# Vibration_Sensor_Schematic_Rev1.net
KiCad netlist of a schematic drawn in EAGLE
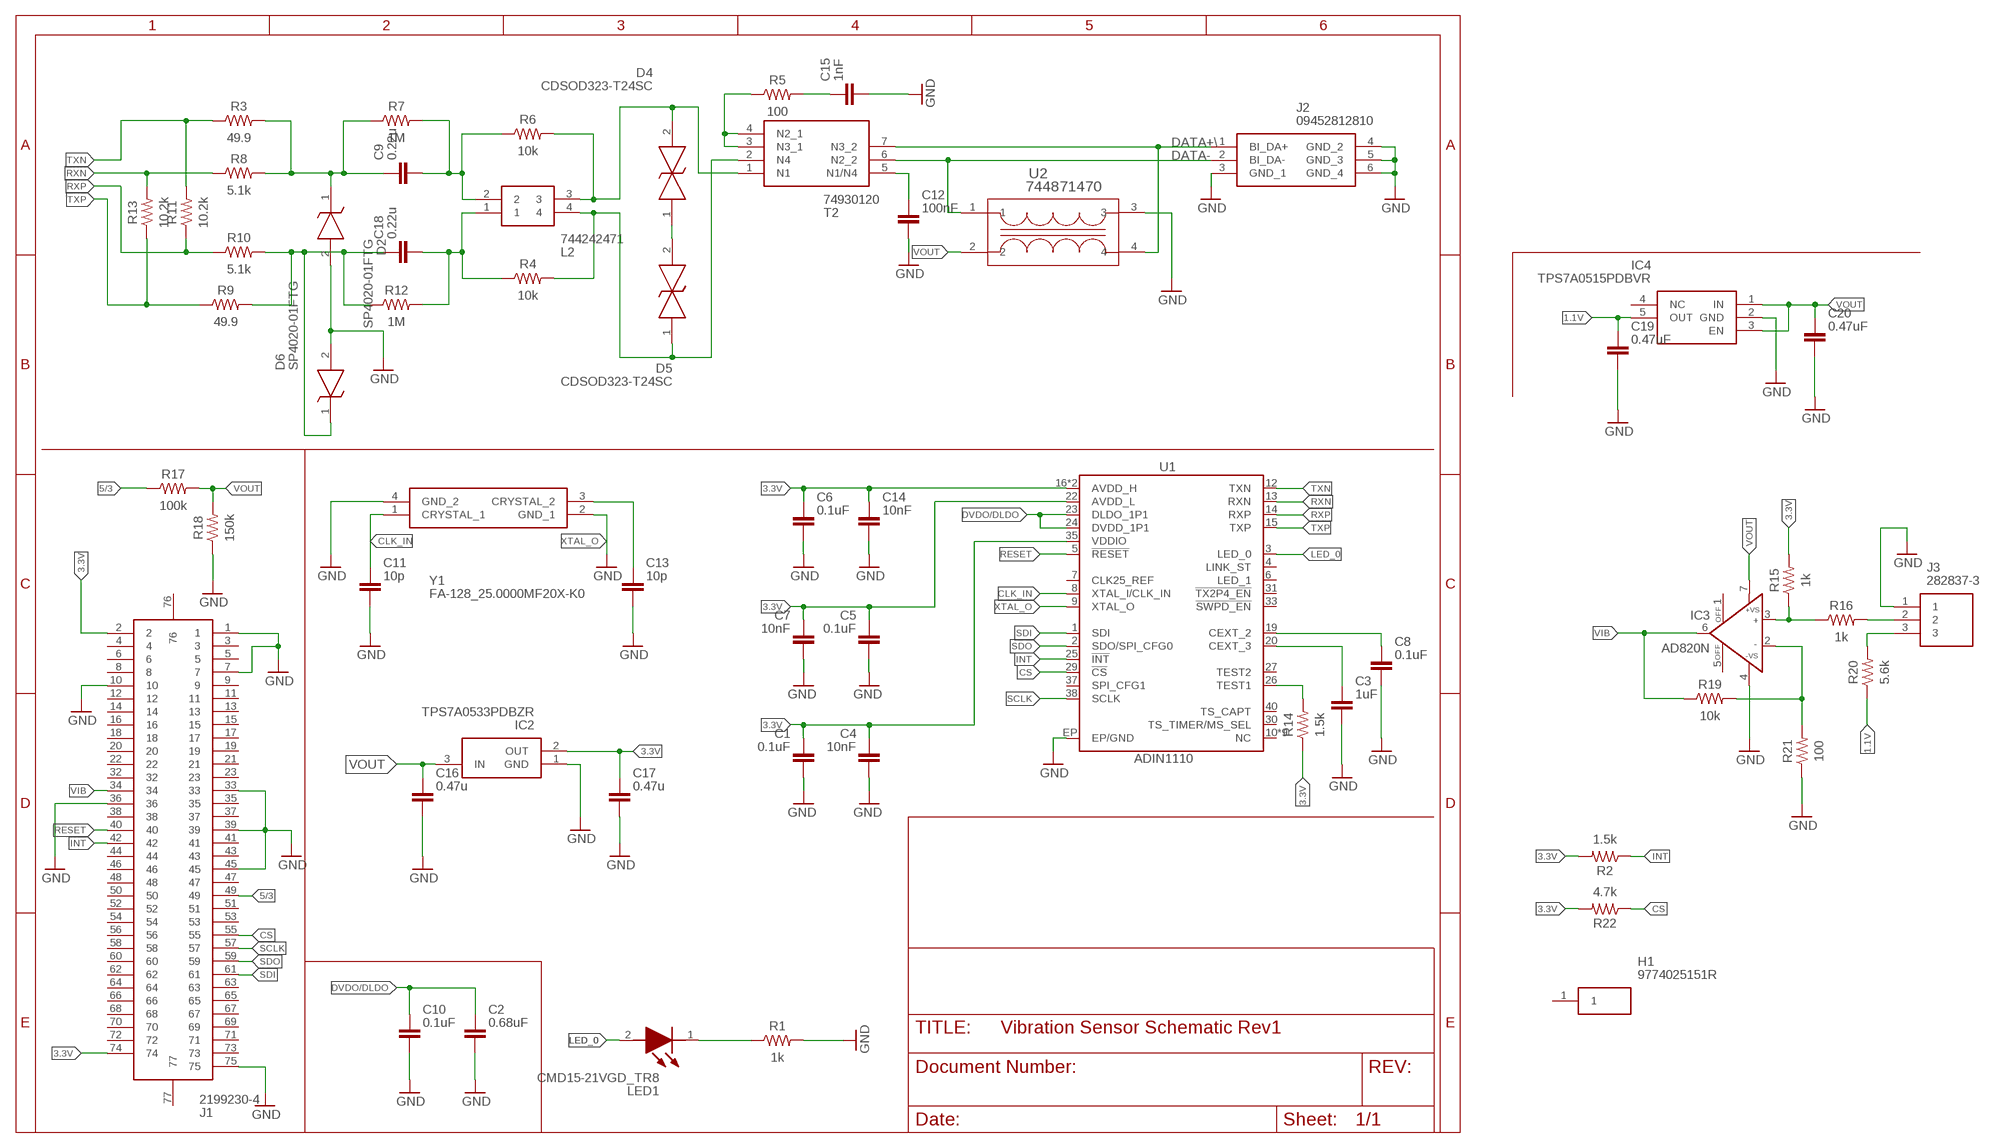
[diagram p0: schematic, sheet 1]

(export (version "E")
  (design (tool "Eeschema 10.0.6"))
  (components
    (comp (ref "C1")
      (value "0.1uF")
      (footprint "eagle-import:CAPC1005X60")
      (libsource (lib "eagle-import") (part "CCHIP-0402(1005-METRIC)_"))
    )
    (comp (ref "C2")
      (value "0.68uF")
      (footprint "eagle-import:CAPC1005X60")
      (libsource (lib "eagle-import") (part "CCHIP-0402(1005-METRIC)_"))
    )
    (comp (ref "C3")
      (value "1uF")
      (footprint "eagle-import:CAPC1005X60")
      (libsource (lib "eagle-import") (part "CCHIP-0402(1005-METRIC)_"))
    )
    (comp (ref "C4")
      (value "10nF")
      (footprint "eagle-import:CAPC1005X60")
      (libsource (lib "eagle-import") (part "CCHIP-0402(1005-METRIC)_"))
    )
    (comp (ref "C5")
      (value "0.1uF")
      (footprint "eagle-import:CAPC1005X60")
      (libsource (lib "eagle-import") (part "CCHIP-0402(1005-METRIC)_"))
    )
    (comp (ref "C6")
      (value "0.1uF")
      (footprint "eagle-import:CAPC1005X60")
      (libsource (lib "eagle-import") (part "CCHIP-0402(1005-METRIC)_"))
    )
    (comp (ref "C7")
      (value "10nF")
      (footprint "eagle-import:CAPC1005X60")
      (libsource (lib "eagle-import") (part "CCHIP-0402(1005-METRIC)_"))
    )
    (comp (ref "C8")
      (value "0.1uF")
      (footprint "eagle-import:CAPC1005X60")
      (libsource (lib "eagle-import") (part "CCHIP-0402(1005-METRIC)_"))
    )
    (comp (ref "C9")
      (value "0.22u")
      (footprint "eagle-import:CAPC1005X60")
      (libsource (lib "eagle-import") (part "CCHIP-0402(1005-METRIC)_"))
    )
    (comp (ref "C10")
      (value "0.1uF")
      (footprint "eagle-import:CAPC1005X60")
      (libsource (lib "eagle-import") (part "CCHIP-0402(1005-METRIC)_"))
    )
    (comp (ref "C11")
      (value "10p")
      (footprint "eagle-import:CAPC1005X60")
      (libsource (lib "eagle-import") (part "CCHIP-0402(1005-METRIC)_"))
    )
    (comp (ref "C12")
      (value "100nF")
      (footprint "eagle-import:CAPC1005X60")
      (libsource (lib "eagle-import") (part "CCHIP-0402(1005-METRIC)_"))
    )
    (comp (ref "C13")
      (value "10p")
      (footprint "eagle-import:CAPC1005X60")
      (libsource (lib "eagle-import") (part "CCHIP-0402(1005-METRIC)_"))
    )
    (comp (ref "C14")
      (value "10nF")
      (footprint "eagle-import:CAPC1005X60")
      (libsource (lib "eagle-import") (part "CCHIP-0402(1005-METRIC)_"))
    )
    (comp (ref "C15")
      (value "1nF")
      (footprint "eagle-import:CAPC1005X60")
      (libsource (lib "eagle-import") (part "CCHIP-0402(1005-METRIC)_"))
    )
    (comp (ref "C16")
      (value "0.47u")
      (footprint "eagle-import:CAPC1005X60")
      (libsource (lib "eagle-import") (part "CCHIP-0402(1005-METRIC)_"))
    )
    (comp (ref "C17")
      (value "0.47u")
      (footprint "eagle-import:CAPC1005X60")
      (libsource (lib "eagle-import") (part "CCHIP-0402(1005-METRIC)_"))
    )
    (comp (ref "C18")
      (value "0.22u")
      (footprint "eagle-import:CAPC1005X60")
      (libsource (lib "eagle-import") (part "CCHIP-0402(1005-METRIC)_"))
    )
    (comp (ref "C19")
      (value "0.47uF")
      (footprint "eagle-import:CAPC1005X60")
      (libsource (lib "eagle-import") (part "CCHIP-0402(1005-METRIC)_"))
    )
    (comp (ref "C20")
      (value "0.47uF")
      (footprint "eagle-import:CAPC1005X60")
      (libsource (lib "eagle-import") (part "CCHIP-0402(1005-METRIC)_"))
    )
    (comp (ref "D2")
      (value "SP4020-01FTG")
      (footprint "eagle-import:SOD2613X114N")
      (fields (field (name "MOUSER_PART_NUMBER") "576-SP4020-01FTG"))
      (libsource (lib "eagle-import") (part "SP4020-01FTG"))
    )
    (comp (ref "D4")
      (value "CDSOD323-T24SC")
      (footprint "eagle-import:SOD2513X114N")
      (fields (field (name "MOUSER_PART_NUMBER") "652-CDSOD323-T24SC"))
      (libsource (lib "eagle-import") (part "CDSOD323-T24SC"))
    )
    (comp (ref "D5")
      (value "CDSOD323-T24SC")
      (footprint "eagle-import:SOD2513X114N")
      (fields (field (name "MOUSER_PART_NUMBER") "652-CDSOD323-T24SC"))
      (libsource (lib "eagle-import") (part "CDSOD323-T24SC"))
    )
    (comp (ref "D6")
      (value "SP4020-01FTG")
      (footprint "eagle-import:SOD2613X114N")
      (fields (field (name "MOUSER_PART_NUMBER") "576-SP4020-01FTG"))
      (libsource (lib "eagle-import") (part "SP4020-01FTG"))
    )
    (comp (ref "H1")
      (value "9774025151R")
      (footprint "eagle-import:9774025151R")
      (fields (field (name "MOUSER_PART_NUMBER") "710-9774025151R"))
      (libsource (lib "eagle-import") (part "9774025151R"))
    )
    (comp (ref "IC2")
      (value "TPS7A0533PDBZR")
      (footprint "eagle-import:SOT95P237X112-3N")
      (fields (field (name "MOUSER_PART_NUMBER") "595-TPS7A0533PDBZR"))
      (libsource (lib "eagle-import") (part "TPS7A0533PDBZR"))
    )
    (comp (ref "IC3")
      (value "AD820N")
      (footprint "eagle-import:DIL08")
      (libsource (lib "eagle-import") (part "AD820N"))
    )
    (comp (ref "IC4")
      (value "TPS7A0515PDBVR")
      (footprint "eagle-import:SOT95P280X145-5N")
      (fields (field (name "MOUSER_PART_NUMBER") "595-TPS7A0515PDBVR"))
      (libsource (lib "eagle-import") (part "TPS7A0515PDBVR"))
    )
    (comp (ref "J1")
      (value "2199230-4")
      (footprint "eagle-import:21992304")
      (fields (field (name "MOUSER_PART_NUMBER") "571-2199230-4"))
      (libsource (lib "eagle-import") (part "2199230-4"))
    )
    (comp (ref "J2")
      (value "09452812810")
      (footprint "eagle-import:09452812810")
      (fields (field (name "MOUSER_PART_NUMBER") "617-09452812810"))
      (libsource (lib "eagle-import") (part "09452812810"))
    )
    (comp (ref "J3")
      (value "282837-3")
      (footprint "eagle-import:2828373")
      (fields (field (name "MOUSER_PART_NUMBER") "571-2828373"))
      (libsource (lib "eagle-import") (part "282837-3"))
    )
    (comp (ref "L2")
      (value "744242471")
      (footprint "eagle-import:744242471")
      (fields (field (name "MOUSER_PART_NUMBER") "710-744242471"))
      (libsource (lib "eagle-import") (part "744242471"))
    )
    (comp (ref "LED1")
      (value "CMD15-21VGD_TR8")
      (footprint "eagle-import:LEDC3215X130N")
      (fields
        (field (name "ARROW_PART_NUMBER") "CMD15-21VGD/TR8")
        (field (name "MOUSER_PART_NUMBER") "606-CMD15-21VGD/TR8")
      )
      (libsource (lib "eagle-import") (part "CMD15-21VGD_TR8"))
    )
    (comp (ref "R1")
      (value "1k")
      (footprint "eagle-import:RESC1005X40")
      (libsource (lib "eagle-import") (part "R-USCHIP-0402(1005-METRIC)_"))
    )
    (comp (ref "R2")
      (value "1.5k")
      (footprint "eagle-import:RESC1005X40")
      (libsource (lib "eagle-import") (part "R-USCHIP-0402(1005-METRIC)_"))
    )
    (comp (ref "R3")
      (value "49.9")
      (footprint "eagle-import:RESC1005X40")
      (libsource (lib "eagle-import") (part "R-USCHIP-0402(1005-METRIC)_"))
    )
    (comp (ref "R4")
      (value "10k")
      (footprint "eagle-import:RESC1005X40")
      (libsource (lib "eagle-import") (part "R-USCHIP-0402(1005-METRIC)_"))
    )
    (comp (ref "R5")
      (value "100")
      (footprint "eagle-import:RESC1005X40")
      (libsource (lib "eagle-import") (part "R-USCHIP-0402(1005-METRIC)_"))
    )
    (comp (ref "R6")
      (value "10k")
      (footprint "eagle-import:RESC1005X40")
      (libsource (lib "eagle-import") (part "R-USCHIP-0402(1005-METRIC)_"))
    )
    (comp (ref "R7")
      (value "1M")
      (footprint "eagle-import:RESC1005X40")
      (libsource (lib "eagle-import") (part "R-USCHIP-0402(1005-METRIC)_"))
    )
    (comp (ref "R8")
      (value "5.1k")
      (footprint "eagle-import:RESC1005X40")
      (libsource (lib "eagle-import") (part "R-USCHIP-0402(1005-METRIC)_"))
    )
    (comp (ref "R9")
      (value "49.9")
      (footprint "eagle-import:RESC1005X40")
      (libsource (lib "eagle-import") (part "R-USCHIP-0402(1005-METRIC)_"))
    )
    (comp (ref "R10")
      (value "5.1k")
      (footprint "eagle-import:RESC1005X40")
      (libsource (lib "eagle-import") (part "R-USCHIP-0402(1005-METRIC)_"))
    )
    (comp (ref "R11")
      (value "10.2k")
      (footprint "eagle-import:RESC1005X40")
      (libsource (lib "eagle-import") (part "R-USCHIP-0402(1005-METRIC)_"))
    )
    (comp (ref "R12")
      (value "1M")
      (footprint "eagle-import:RESC1005X40")
      (libsource (lib "eagle-import") (part "R-USCHIP-0402(1005-METRIC)_"))
    )
    (comp (ref "R13")
      (value "10.2k")
      (footprint "eagle-import:RESC1005X40")
      (libsource (lib "eagle-import") (part "R-USCHIP-0402(1005-METRIC)_"))
    )
    (comp (ref "R14")
      (value "1.5k")
      (footprint "eagle-import:RESC1005X40")
      (libsource (lib "eagle-import") (part "R-USCHIP-0402(1005-METRIC)_"))
    )
    (comp (ref "R15")
      (value "1k")
      (footprint "eagle-import:RESC1005X40")
      (libsource (lib "eagle-import") (part "R-USCHIP-0402(1005-METRIC)_"))
    )
    (comp (ref "R16")
      (value "1k")
      (footprint "eagle-import:RESC1005X40")
      (libsource (lib "eagle-import") (part "R-USCHIP-0402(1005-METRIC)_"))
    )
    (comp (ref "R17")
      (value "100k")
      (footprint "eagle-import:RESC1005X40")
      (libsource (lib "eagle-import") (part "R-USCHIP-0402(1005-METRIC)_"))
    )
    (comp (ref "R18")
      (value "150k")
      (footprint "eagle-import:RESC1005X40")
      (libsource (lib "eagle-import") (part "R-USCHIP-0402(1005-METRIC)_"))
    )
    (comp (ref "R19")
      (value "10k")
      (footprint "eagle-import:RESC1005X40")
      (libsource (lib "eagle-import") (part "R-USCHIP-0402(1005-METRIC)_"))
    )
    (comp (ref "R20")
      (value "5.6k")
      (footprint "eagle-import:RESC1005X40")
      (libsource (lib "eagle-import") (part "R-USCHIP-0402(1005-METRIC)_"))
    )
    (comp (ref "R21")
      (value "100")
      (footprint "eagle-import:RESC1005X40")
      (libsource (lib "eagle-import") (part "R-USCHIP-0402(1005-METRIC)_"))
    )
    (comp (ref "R22")
      (value "4.7k")
      (footprint "eagle-import:RESC1005X40")
      (libsource (lib "eagle-import") (part "R-USCHIP-0402(1005-METRIC)_"))
    )
    (comp (ref "T2")
      (value "74930120")
      (footprint "eagle-import:74930120")
      (fields (field (name "MOUSER_PART_NUMBER") "710-74930120"))
      (libsource (lib "eagle-import") (part "74930120"))
    )
    (comp (ref "U1")
      (value "ADIN1110")
      (footprint "eagle-import:LFCSP-40")
      (libsource (lib "eagle-import") (part "ADIN1110"))
    )
    (comp (ref "U2")
      (value "744871470")
      (footprint "eagle-import:SMT_871470_WRE")
      (fields (field (name "COPYRIGHT") "Copyright (C) 2023 Ultra Librarian. All rights reserved."))
      (libsource (lib "eagle-import") (part "744871470"))
    )
    (comp (ref "Y1")
      (value "FA-128_25.0000MF20X-K0")
      (footprint "eagle-import:FA128250000MF20XK0")
      (fields
        (field (name "MANUFACTURER_PART_NUMBER") "FA-128 25.0000MF20X-K0")
        (field (name "MOUSER_PART_NUMBER") "732-FA-12825F20X-K0")
      )
      (libsource (lib "eagle-import") (part "FA-128_25.0000MF20X-K0"))
    )
  )
  (nets
    (net (code "1") (name "/DATA+\\") (class "Default")
      (node (ref "J2") (pin "1") (pinfunction "BI_DA+_1") (pintype "bidirectional"))
      (node (ref "T2") (pin "7") (pinfunction "N3_2_7") (pintype "bidirectional"))
      (node (ref "U2") (pin "4") (pinfunction "4_4") (pintype "passive"))
    )
    (net (code "2") (name "/DATA-") (class "Default")
      (node (ref "J2") (pin "2") (pinfunction "BI_DA-_2") (pintype "bidirectional"))
      (node (ref "T2") (pin "6") (pinfunction "N2_2_6") (pintype "bidirectional"))
      (node (ref "U2") (pin "1") (pinfunction "1_1") (pintype "passive"))
    )
    (net (code "3") (name "1.1V") (class "Default")
      (node (ref "C19") (pin "1") (pinfunction "1_1") (pintype "passive"))
      (node (ref "IC4") (pin "5") (pinfunction "OUT_5") (pintype "bidirectional"))
      (node (ref "R20") (pin "1") (pinfunction "1_1") (pintype "passive"))
    )
    (net (code "4") (name "3.3V") (class "Default")
      (node (ref "C1") (pin "1") (pinfunction "1_1") (pintype "passive"))
      (node (ref "C14") (pin "1") (pinfunction "1_1") (pintype "passive"))
      (node (ref "C17") (pin "1") (pinfunction "1_1") (pintype "passive"))
      (node (ref "C4") (pin "1") (pinfunction "1_1") (pintype "passive"))
      (node (ref "C5") (pin "1") (pinfunction "1_1") (pintype "passive"))
      (node (ref "C6") (pin "1") (pinfunction "1_1") (pintype "passive"))
      (node (ref "C7") (pin "1") (pinfunction "1_1") (pintype "passive"))
      (node (ref "IC2") (pin "2") (pinfunction "OUT_2") (pintype "output"))
      (node (ref "J1") (pin "2") (pinfunction "2_2") (pintype "bidirectional"))
      (node (ref "J1") (pin "74") (pinfunction "74_74") (pintype "bidirectional"))
      (node (ref "R14") (pin "1") (pinfunction "1_1") (pintype "passive"))
      (node (ref "R15") (pin "2") (pinfunction "2_2") (pintype "passive"))
      (node (ref "R2") (pin "2") (pinfunction "2_2") (pintype "passive"))
      (node (ref "R22") (pin "2") (pinfunction "2_2") (pintype "passive"))
      (node (ref "U1") (pin "16") (pinfunction "AVDD_H_16") (pintype "bidirectional"))
      (node (ref "U1") (pin "17") (pinfunction "AVDD_H_17") (pintype "bidirectional"))
      (node (ref "U1") (pin "22") (pinfunction "AVDD_L_22") (pintype "bidirectional"))
      (node (ref "U1") (pin "35") (pinfunction "VDDIO_35") (pintype "bidirectional"))
    )
    (net (code "5") (name "5{slash}3") (class "Default")
      (node (ref "J1") (pin "49") (pinfunction "49_49") (pintype "bidirectional"))
      (node (ref "R17") (pin "1") (pinfunction "1_1") (pintype "passive"))
    )
    (net (code "6") (name "CLK_IN") (class "Default")
      (node (ref "C11") (pin "1") (pinfunction "1_1") (pintype "passive"))
      (node (ref "U1") (pin "8") (pinfunction "XTAL_I/CLK_IN_8") (pintype "bidirectional"))
      (node (ref "Y1") (pin "1") (pinfunction "CRYSTAL_1_1") (pintype "bidirectional"))
    )
    (net (code "7") (name "CS") (class "Default")
      (node (ref "J1") (pin "55") (pinfunction "55_55") (pintype "bidirectional"))
      (node (ref "R22") (pin "1") (pinfunction "1_1") (pintype "passive"))
      (node (ref "U1") (pin "29") (pinfunction "~{CS}_29") (pintype "bidirectional"))
    )
    (net (code "8") (name "DVDO{slash}DLDO") (class "Default")
      (node (ref "C10") (pin "1") (pinfunction "1_1") (pintype "passive"))
      (node (ref "C2") (pin "1") (pinfunction "1_1") (pintype "passive"))
      (node (ref "U1") (pin "23") (pinfunction "DLDO_1P1_23") (pintype "bidirectional"))
      (node (ref "U1") (pin "24") (pinfunction "DVDD_1P1_24") (pintype "bidirectional"))
    )
    (net (code "9") (name "GND") (class "Default")
      (node (ref "C1") (pin "2") (pinfunction "2_2") (pintype "passive"))
      (node (ref "C10") (pin "2") (pinfunction "2_2") (pintype "passive"))
      (node (ref "C11") (pin "2") (pinfunction "2_2") (pintype "passive"))
      (node (ref "C12") (pin "2") (pinfunction "2_2") (pintype "passive"))
      (node (ref "C13") (pin "2") (pinfunction "2_2") (pintype "passive"))
      (node (ref "C14") (pin "2") (pinfunction "2_2") (pintype "passive"))
      (node (ref "C15") (pin "2") (pinfunction "2_2") (pintype "passive"))
      (node (ref "C16") (pin "2") (pinfunction "2_2") (pintype "passive"))
      (node (ref "C17") (pin "2") (pinfunction "2_2") (pintype "passive"))
      (node (ref "C19") (pin "2") (pinfunction "2_2") (pintype "passive"))
      (node (ref "C2") (pin "2") (pinfunction "2_2") (pintype "passive"))
      (node (ref "C20") (pin "2") (pinfunction "2_2") (pintype "passive"))
      (node (ref "C3") (pin "2") (pinfunction "2_2") (pintype "passive"))
      (node (ref "C4") (pin "2") (pinfunction "2_2") (pintype "passive"))
      (node (ref "C5") (pin "2") (pinfunction "2_2") (pintype "passive"))
      (node (ref "C6") (pin "2") (pinfunction "2_2") (pintype "passive"))
      (node (ref "C7") (pin "2") (pinfunction "2_2") (pintype "passive"))
      (node (ref "C8") (pin "2") (pinfunction "2_2") (pintype "passive"))
      (node (ref "D2") (pin "2") (pinfunction "A_2") (pintype "bidirectional"))
      (node (ref "D6") (pin "2") (pinfunction "A_2") (pintype "bidirectional"))
      (node (ref "IC2") (pin "1") (pinfunction "GND_1") (pintype "power_in"))
      (node (ref "IC3") (pin "4") (pinfunction "-VS_4") (pintype "input"))
      (node (ref "IC4") (pin "2") (pinfunction "GND_2") (pintype "bidirectional"))
      (node (ref "J1") (pin "1") (pinfunction "1_1") (pintype "bidirectional"))
      (node (ref "J1") (pin "10") (pinfunction "10_10") (pintype "bidirectional"))
      (node (ref "J1") (pin "33") (pinfunction "33_33") (pintype "bidirectional"))
      (node (ref "J1") (pin "36") (pinfunction "36_36") (pintype "bidirectional"))
      (node (ref "J1") (pin "39") (pinfunction "39_39") (pintype "bidirectional"))
      (node (ref "J1") (pin "45") (pinfunction "45_45") (pintype "bidirectional"))
      (node (ref "J1") (pin "7") (pinfunction "7_7") (pintype "bidirectional"))
      (node (ref "J1") (pin "75") (pinfunction "75_75") (pintype "bidirectional"))
      (node (ref "J2") (pin "3") (pinfunction "GND_1_3") (pintype "bidirectional"))
      (node (ref "J2") (pin "4") (pinfunction "GND_2_4") (pintype "bidirectional"))
      (node (ref "J2") (pin "5") (pinfunction "GND_3_5") (pintype "bidirectional"))
      (node (ref "J2") (pin "6") (pinfunction "GND_4_6") (pintype "bidirectional"))
      (node (ref "J3") (pin "1") (pinfunction "1_1") (pintype "bidirectional"))
      (node (ref "R1") (pin "2") (pinfunction "2_2") (pintype "passive"))
      (node (ref "R18") (pin "1") (pinfunction "1_1") (pintype "passive"))
      (node (ref "R21") (pin "1") (pinfunction "1_1") (pintype "passive"))
      (node (ref "U1") (pin "EP") (pinfunction "EP/GND_EP") (pintype "bidirectional"))
      (node (ref "U2") (pin "3") (pinfunction "3_3") (pintype "passive"))
      (node (ref "Y1") (pin "2") (pinfunction "GND_1_2") (pintype "bidirectional"))
      (node (ref "Y1") (pin "4") (pinfunction "GND_2_4") (pintype "bidirectional"))
    )
    (net (code "10") (name "INT") (class "Default")
      (node (ref "J1") (pin "42") (pinfunction "42_42") (pintype "bidirectional"))
      (node (ref "R2") (pin "1") (pinfunction "1_1") (pintype "passive"))
      (node (ref "U1") (pin "25") (pinfunction "~{INT}_25") (pintype "bidirectional"))
    )
    (net (code "11") (name "LED_0") (class "Default")
      (node (ref "LED1") (pin "2") (pinfunction "A_2") (pintype "bidirectional"))
      (node (ref "U1") (pin "3") (pinfunction "LED_0_3") (pintype "bidirectional"))
    )
    (net (code "12") (name "Net-(C9-Pad2)") (class "Default")
      (node (ref "C9") (pin "2") (pinfunction "2_2") (pintype "passive"))
      (node (ref "L2") (pin "2") (pinfunction "2_2") (pintype "bidirectional"))
      (node (ref "R6") (pin "1") (pinfunction "1_1") (pintype "passive"))
      (node (ref "R7") (pin "2") (pinfunction "2_2") (pintype "passive"))
    )
    (net (code "13") (name "Net-(C15-Pad1)") (class "Default")
      (node (ref "C15") (pin "1") (pinfunction "1_1") (pintype "passive"))
      (node (ref "R5") (pin "2") (pinfunction "2_2") (pintype "passive"))
    )
    (net (code "14") (name "Net-(C18-Pad2)") (class "Default")
      (node (ref "C18") (pin "2") (pinfunction "2_2") (pintype "passive"))
      (node (ref "L2") (pin "1") (pinfunction "1_1") (pintype "bidirectional"))
      (node (ref "R12") (pin "2") (pinfunction "2_2") (pintype "passive"))
      (node (ref "R4") (pin "1") (pinfunction "1_1") (pintype "passive"))
    )
    (net (code "15") (name "Net-(D2-K)") (class "Default")
      (node (ref "C9") (pin "1") (pinfunction "1_1") (pintype "passive"))
      (node (ref "D2") (pin "1") (pinfunction "K_1") (pintype "bidirectional"))
      (node (ref "R3") (pin "2") (pinfunction "2_2") (pintype "passive"))
      (node (ref "R7") (pin "1") (pinfunction "1_1") (pintype "passive"))
      (node (ref "R8") (pin "2") (pinfunction "2_2") (pintype "passive"))
    )
    (net (code "16") (name "Net-(D4-Pad1)") (class "Default")
      (node (ref "D4") (pin "1") (pinfunction "1_1") (pintype "bidirectional"))
      (node (ref "D5") (pin "2") (pinfunction "2_2") (pintype "bidirectional"))
    )
    (net (code "17") (name "Net-(D6-K)") (class "Default")
      (node (ref "C18") (pin "1") (pinfunction "1_1") (pintype "passive"))
      (node (ref "D6") (pin "1") (pinfunction "K_1") (pintype "bidirectional"))
      (node (ref "R10") (pin "2") (pinfunction "2_2") (pintype "passive"))
      (node (ref "R12") (pin "1") (pinfunction "1_1") (pintype "passive"))
      (node (ref "R9") (pin "2") (pinfunction "2_2") (pintype "passive"))
    )
    (net (code "18") (name "Net-(IC3-IN+)") (class "Default")
      (node (ref "IC3") (pin "3") (pinfunction "IN+_3") (pintype "input"))
      (node (ref "R15") (pin "1") (pinfunction "1_1") (pintype "passive"))
      (node (ref "R16") (pin "1") (pinfunction "1_1") (pintype "passive"))
    )
    (net (code "19") (name "Net-(IC3-IN-)") (class "Default")
      (node (ref "IC3") (pin "2") (pinfunction "IN-_2") (pintype "input"))
      (node (ref "R19") (pin "2") (pinfunction "2_2") (pintype "passive"))
      (node (ref "R21") (pin "2") (pinfunction "2_2") (pintype "passive"))
    )
    (net (code "20") (name "Net-(J3-Pad2)") (class "Default")
      (node (ref "J3") (pin "2") (pinfunction "2_2") (pintype "bidirectional"))
      (node (ref "R16") (pin "2") (pinfunction "2_2") (pintype "passive"))
    )
    (net (code "21") (name "Net-(J3-Pad3)") (class "Default")
      (node (ref "J3") (pin "3") (pinfunction "3_3") (pintype "bidirectional"))
      (node (ref "R20") (pin "2") (pinfunction "2_2") (pintype "passive"))
    )
    (net (code "22") (name "Net-(LED1-K)") (class "Default")
      (node (ref "LED1") (pin "1") (pinfunction "K_1") (pintype "bidirectional"))
      (node (ref "R1") (pin "1") (pinfunction "1_1") (pintype "passive"))
    )
    (net (code "23") (name "Net-(T2-N1)") (class "Default")
      (node (ref "D4") (pin "2") (pinfunction "2_2") (pintype "bidirectional"))
      (node (ref "L2") (pin "3") (pinfunction "3_3") (pintype "bidirectional"))
      (node (ref "R6") (pin "2") (pinfunction "2_2") (pintype "passive"))
      (node (ref "T2") (pin "1") (pinfunction "N1_1") (pintype "bidirectional"))
    )
    (net (code "24") (name "Net-(T2-N1{slash}N4)") (class "Default")
      (node (ref "C12") (pin "1") (pinfunction "1_1") (pintype "passive"))
      (node (ref "T2") (pin "5") (pinfunction "N1/N4_5") (pintype "bidirectional"))
    )
    (net (code "25") (name "Net-(T2-N2_1)") (class "Default")
      (node (ref "R5") (pin "1") (pinfunction "1_1") (pintype "passive"))
      (node (ref "T2") (pin "3") (pinfunction "N3_1_3") (pintype "bidirectional"))
      (node (ref "T2") (pin "4") (pinfunction "N2_1_4") (pintype "bidirectional"))
    )
    (net (code "26") (name "Net-(T2-N4)") (class "Default")
      (node (ref "D5") (pin "1") (pinfunction "1_1") (pintype "bidirectional"))
      (node (ref "L2") (pin "4") (pinfunction "4_4") (pintype "bidirectional"))
      (node (ref "R4") (pin "2") (pinfunction "2_2") (pintype "passive"))
      (node (ref "T2") (pin "2") (pinfunction "N4_2") (pintype "bidirectional"))
    )
    (net (code "27") (name "Net-(U1-CEXT_2)") (class "Default")
      (node (ref "C8") (pin "1") (pinfunction "1_1") (pintype "passive"))
      (node (ref "U1") (pin "19") (pinfunction "CEXT_2_19") (pintype "bidirectional"))
    )
    (net (code "28") (name "Net-(U1-CEXT_3)") (class "Default")
      (node (ref "C3") (pin "1") (pinfunction "1_1") (pintype "passive"))
      (node (ref "U1") (pin "20") (pinfunction "CEXT_3_20") (pintype "bidirectional"))
    )
    (net (code "29") (name "Net-(U1-TEST1)") (class "Default")
      (node (ref "R14") (pin "2") (pinfunction "2_2") (pintype "passive"))
      (node (ref "U1") (pin "26") (pinfunction "TEST1_26") (pintype "bidirectional"))
    )
    (net (code "30") (name "RESET") (class "Default")
      (node (ref "J1") (pin "40") (pinfunction "40_40") (pintype "bidirectional"))
      (node (ref "U1") (pin "5") (pinfunction "~{RESET}_5") (pintype "bidirectional"))
    )
    (net (code "31") (name "RXN") (class "Default")
      (node (ref "R13") (pin "2") (pinfunction "2_2") (pintype "passive"))
      (node (ref "R8") (pin "1") (pinfunction "1_1") (pintype "passive"))
      (node (ref "U1") (pin "13") (pinfunction "RXN_13") (pintype "bidirectional"))
    )
    (net (code "32") (name "RXP") (class "Default")
      (node (ref "R10") (pin "1") (pinfunction "1_1") (pintype "passive"))
      (node (ref "R11") (pin "1") (pinfunction "1_1") (pintype "passive"))
      (node (ref "U1") (pin "14") (pinfunction "RXP_14") (pintype "bidirectional"))
    )
    (net (code "33") (name "SCLK") (class "Default")
      (node (ref "J1") (pin "57") (pinfunction "57_57") (pintype "bidirectional"))
      (node (ref "U1") (pin "38") (pinfunction "SCLK_38") (pintype "bidirectional"))
    )
    (net (code "34") (name "SDI") (class "Default")
      (node (ref "J1") (pin "61") (pinfunction "61_61") (pintype "bidirectional"))
      (node (ref "U1") (pin "1") (pinfunction "SDI_1") (pintype "bidirectional"))
    )
    (net (code "35") (name "SDO") (class "Default")
      (node (ref "J1") (pin "59") (pinfunction "59_59") (pintype "bidirectional"))
      (node (ref "U1") (pin "2") (pinfunction "SDO/SPI_CFG0_2") (pintype "bidirectional"))
    )
    (net (code "36") (name "TXN") (class "Default")
      (node (ref "R11") (pin "2") (pinfunction "2_2") (pintype "passive"))
      (node (ref "R3") (pin "1") (pinfunction "1_1") (pintype "passive"))
      (node (ref "U1") (pin "12") (pinfunction "TXN_12") (pintype "bidirectional"))
    )
    (net (code "37") (name "TXP") (class "Default")
      (node (ref "R13") (pin "1") (pinfunction "1_1") (pintype "passive"))
      (node (ref "R9") (pin "1") (pinfunction "1_1") (pintype "passive"))
      (node (ref "U1") (pin "15") (pinfunction "TXP_15") (pintype "bidirectional"))
    )
    (net (code "38") (name "VIB") (class "Default")
      (node (ref "IC3") (pin "6") (pinfunction "OUT_6") (pintype "output"))
      (node (ref "J1") (pin "34") (pinfunction "34_34") (pintype "bidirectional"))
      (node (ref "R19") (pin "1") (pinfunction "1_1") (pintype "passive"))
    )
    (net (code "39") (name "VOUT") (class "Default")
      (node (ref "C16") (pin "1") (pinfunction "1_1") (pintype "passive"))
      (node (ref "C20") (pin "1") (pinfunction "1_1") (pintype "passive"))
      (node (ref "IC2") (pin "3") (pinfunction "IN_3") (pintype "input"))
      (node (ref "IC3") (pin "7") (pinfunction "+VS_7") (pintype "input"))
      (node (ref "IC4") (pin "1") (pinfunction "IN_1") (pintype "bidirectional"))
      (node (ref "IC4") (pin "3") (pinfunction "EN_3") (pintype "bidirectional"))
      (node (ref "R17") (pin "2") (pinfunction "2_2") (pintype "passive"))
      (node (ref "R18") (pin "2") (pinfunction "2_2") (pintype "passive"))
      (node (ref "U2") (pin "2") (pinfunction "2_2") (pintype "passive"))
    )
    (net (code "40") (name "XTAL_O") (class "Default")
      (node (ref "C13") (pin "1") (pinfunction "1_1") (pintype "passive"))
      (node (ref "U1") (pin "9") (pinfunction "XTAL_O_9") (pintype "bidirectional"))
      (node (ref "Y1") (pin "3") (pinfunction "CRYSTAL_2_3") (pintype "bidirectional"))
    )
    (net (code "41") (name "unconnected-(H1-Pad1)") (class "Default")
      (node (ref "H1") (pin "1") (pinfunction "1_1") (pintype "bidirectional"))
    )
    (net (code "42") (name "unconnected-(IC3-OFF-Pad1)") (class "Default")
      (node (ref "IC3") (pin "1") (pinfunction "OFF_1") (pintype "passive"))
    )
    (net (code "43") (name "unconnected-(IC3-OFF-Pad5)") (class "Default")
      (node (ref "IC3") (pin "5") (pinfunction "OFF_5") (pintype "passive"))
    )
    (net (code "44") (name "unconnected-(IC4-NC-Pad4)") (class "Default")
      (node (ref "IC4") (pin "4") (pinfunction "NC_4") (pintype "no_connect"))
    )
    (net (code "45") (name "unconnected-(J1-Pad3)") (class "Default")
      (node (ref "J1") (pin "3") (pinfunction "3_3") (pintype "bidirectional"))
    )
    (net (code "46") (name "unconnected-(J1-Pad4)") (class "Default")
      (node (ref "J1") (pin "4") (pinfunction "4_4") (pintype "bidirectional"))
    )
    (net (code "47") (name "unconnected-(J1-Pad5)") (class "Default")
      (node (ref "J1") (pin "5") (pinfunction "5_5") (pintype "bidirectional"))
    )
    (net (code "48") (name "unconnected-(J1-Pad6)") (class "Default")
      (node (ref "J1") (pin "6") (pinfunction "6_6") (pintype "bidirectional"))
    )
    (net (code "49") (name "unconnected-(J1-Pad8)") (class "Default")
      (node (ref "J1") (pin "8") (pinfunction "8_8") (pintype "bidirectional"))
    )
    (net (code "50") (name "unconnected-(J1-Pad9)") (class "Default")
      (node (ref "J1") (pin "9") (pinfunction "9_9") (pintype "bidirectional"))
    )
    (net (code "51") (name "unconnected-(J1-Pad11)") (class "Default")
      (node (ref "J1") (pin "11") (pinfunction "11_11") (pintype "bidirectional"))
    )
    (net (code "52") (name "unconnected-(J1-Pad12)") (class "Default")
      (node (ref "J1") (pin "12") (pinfunction "12_12") (pintype "bidirectional"))
    )
    (net (code "53") (name "unconnected-(J1-Pad13)") (class "Default")
      (node (ref "J1") (pin "13") (pinfunction "13_13") (pintype "bidirectional"))
    )
    (net (code "54") (name "unconnected-(J1-Pad14)") (class "Default")
      (node (ref "J1") (pin "14") (pinfunction "14_14") (pintype "bidirectional"))
    )
    (net (code "55") (name "unconnected-(J1-Pad15)") (class "Default")
      (node (ref "J1") (pin "15") (pinfunction "15_15") (pintype "bidirectional"))
    )
    (net (code "56") (name "unconnected-(J1-Pad16)") (class "Default")
      (node (ref "J1") (pin "16") (pinfunction "16_16") (pintype "bidirectional"))
    )
    (net (code "57") (name "unconnected-(J1-Pad17)") (class "Default")
      (node (ref "J1") (pin "17") (pinfunction "17_17") (pintype "bidirectional"))
    )
    (net (code "58") (name "unconnected-(J1-Pad18)") (class "Default")
      (node (ref "J1") (pin "18") (pinfunction "18_18") (pintype "bidirectional"))
    )
    (net (code "59") (name "unconnected-(J1-Pad19)") (class "Default")
      (node (ref "J1") (pin "19") (pinfunction "19_19") (pintype "bidirectional"))
    )
    (net (code "60") (name "unconnected-(J1-Pad20)") (class "Default")
      (node (ref "J1") (pin "20") (pinfunction "20_20") (pintype "bidirectional"))
    )
    (net (code "61") (name "unconnected-(J1-Pad21)") (class "Default")
      (node (ref "J1") (pin "21") (pinfunction "21_21") (pintype "bidirectional"))
    )
    (net (code "62") (name "unconnected-(J1-Pad22)") (class "Default")
      (node (ref "J1") (pin "22") (pinfunction "22_22") (pintype "bidirectional"))
    )
    (net (code "63") (name "unconnected-(J1-Pad23)") (class "Default")
      (node (ref "J1") (pin "23") (pinfunction "23_23") (pintype "bidirectional"))
    )
    (net (code "64") (name "unconnected-(J1-Pad32)") (class "Default")
      (node (ref "J1") (pin "32") (pinfunction "32_32") (pintype "bidirectional"))
    )
    (net (code "65") (name "unconnected-(J1-Pad35)") (class "Default")
      (node (ref "J1") (pin "35") (pinfunction "35_35") (pintype "bidirectional"))
    )
    (net (code "66") (name "unconnected-(J1-Pad37)") (class "Default")
      (node (ref "J1") (pin "37") (pinfunction "37_37") (pintype "bidirectional"))
    )
    (net (code "67") (name "unconnected-(J1-Pad38)") (class "Default")
      (node (ref "J1") (pin "38") (pinfunction "38_38") (pintype "bidirectional"))
    )
    (net (code "68") (name "unconnected-(J1-Pad41)") (class "Default")
      (node (ref "J1") (pin "41") (pinfunction "41_41") (pintype "bidirectional"))
    )
    (net (code "69") (name "unconnected-(J1-Pad43)") (class "Default")
      (node (ref "J1") (pin "43") (pinfunction "43_43") (pintype "bidirectional"))
    )
    (net (code "70") (name "unconnected-(J1-Pad44)") (class "Default")
      (node (ref "J1") (pin "44") (pinfunction "44_44") (pintype "bidirectional"))
    )
    (net (code "71") (name "unconnected-(J1-Pad46)") (class "Default")
      (node (ref "J1") (pin "46") (pinfunction "46_46") (pintype "bidirectional"))
    )
    (net (code "72") (name "unconnected-(J1-Pad47)") (class "Default")
      (node (ref "J1") (pin "47") (pinfunction "47_47") (pintype "bidirectional"))
    )
    (net (code "73") (name "unconnected-(J1-Pad48)") (class "Default")
      (node (ref "J1") (pin "48") (pinfunction "48_48") (pintype "bidirectional"))
    )
    (net (code "74") (name "unconnected-(J1-Pad50)") (class "Default")
      (node (ref "J1") (pin "50") (pinfunction "50_50") (pintype "bidirectional"))
    )
    (net (code "75") (name "unconnected-(J1-Pad51)") (class "Default")
      (node (ref "J1") (pin "51") (pinfunction "51_51") (pintype "bidirectional"))
    )
    (net (code "76") (name "unconnected-(J1-Pad52)") (class "Default")
      (node (ref "J1") (pin "52") (pinfunction "52_52") (pintype "bidirectional"))
    )
    (net (code "77") (name "unconnected-(J1-Pad53)") (class "Default")
      (node (ref "J1") (pin "53") (pinfunction "53_53") (pintype "bidirectional"))
    )
    (net (code "78") (name "unconnected-(J1-Pad54)") (class "Default")
      (node (ref "J1") (pin "54") (pinfunction "54_54") (pintype "bidirectional"))
    )
    (net (code "79") (name "unconnected-(J1-Pad56)") (class "Default")
      (node (ref "J1") (pin "56") (pinfunction "56_56") (pintype "bidirectional"))
    )
    (net (code "80") (name "unconnected-(J1-Pad58)") (class "Default")
      (node (ref "J1") (pin "58") (pinfunction "58_58") (pintype "bidirectional"))
    )
    (net (code "81") (name "unconnected-(J1-Pad60)") (class "Default")
      (node (ref "J1") (pin "60") (pinfunction "60_60") (pintype "bidirectional"))
    )
    (net (code "82") (name "unconnected-(J1-Pad62)") (class "Default")
      (node (ref "J1") (pin "62") (pinfunction "62_62") (pintype "bidirectional"))
    )
    (net (code "83") (name "unconnected-(J1-Pad63)") (class "Default")
      (node (ref "J1") (pin "63") (pinfunction "63_63") (pintype "bidirectional"))
    )
    (net (code "84") (name "unconnected-(J1-Pad64)") (class "Default")
      (node (ref "J1") (pin "64") (pinfunction "64_64") (pintype "bidirectional"))
    )
    (net (code "85") (name "unconnected-(J1-Pad65)") (class "Default")
      (node (ref "J1") (pin "65") (pinfunction "65_65") (pintype "bidirectional"))
    )
    (net (code "86") (name "unconnected-(J1-Pad66)") (class "Default")
      (node (ref "J1") (pin "66") (pinfunction "66_66") (pintype "bidirectional"))
    )
    (net (code "87") (name "unconnected-(J1-Pad67)") (class "Default")
      (node (ref "J1") (pin "67") (pinfunction "67_67") (pintype "bidirectional"))
    )
    (net (code "88") (name "unconnected-(J1-Pad68)") (class "Default")
      (node (ref "J1") (pin "68") (pinfunction "68_68") (pintype "bidirectional"))
    )
    (net (code "89") (name "unconnected-(J1-Pad69)") (class "Default")
      (node (ref "J1") (pin "69") (pinfunction "69_69") (pintype "bidirectional"))
    )
    (net (code "90") (name "unconnected-(J1-Pad70)") (class "Default")
      (node (ref "J1") (pin "70") (pinfunction "70_70") (pintype "bidirectional"))
    )
    (net (code "91") (name "unconnected-(J1-Pad71)") (class "Default")
      (node (ref "J1") (pin "71") (pinfunction "71_71") (pintype "bidirectional"))
    )
    (net (code "92") (name "unconnected-(J1-Pad72)") (class "Default")
      (node (ref "J1") (pin "72") (pinfunction "72_72") (pintype "bidirectional"))
    )
    (net (code "93") (name "unconnected-(J1-Pad73)") (class "Default")
      (node (ref "J1") (pin "73") (pinfunction "73_73") (pintype "bidirectional"))
    )
    (net (code "94") (name "unconnected-(J1-Pad76)") (class "Default")
      (node (ref "J1") (pin "76") (pinfunction "76_76") (pintype "bidirectional"))
    )
    (net (code "95") (name "unconnected-(J1-Pad77)") (class "Default")
      (node (ref "J1") (pin "77") (pinfunction "77_77") (pintype "bidirectional"))
    )
    (net (code "96") (name "unconnected-(U1-CLK25_REF-Pad7)") (class "Default")
      (node (ref "U1") (pin "7") (pinfunction "CLK25_REF_7") (pintype "bidirectional"))
    )
    (net (code "97") (name "unconnected-(U1-LED_1-Pad6)") (class "Default")
      (node (ref "U1") (pin "6") (pinfunction "LED_1_6") (pintype "bidirectional"))
    )
    (net (code "98") (name "unconnected-(U1-LINK_ST-Pad4)") (class "Default")
      (node (ref "U1") (pin "4") (pinfunction "LINK_ST_4") (pintype "bidirectional"))
    )
    (net (code "99") (name "unconnected-(U1-NC-Pad10)") (class "Default")
      (node (ref "U1") (pin "10") (pinfunction "NC_10") (pintype "no_connect"))
    )
    (net (code "100") (name "unconnected-(U1-NC-Pad11)") (class "Default")
      (node (ref "U1") (pin "11") (pinfunction "NC_11") (pintype "no_connect"))
    )
    (net (code "101") (name "unconnected-(U1-NC-Pad18)") (class "Default")
      (node (ref "U1") (pin "18") (pinfunction "NC_18") (pintype "no_connect"))
    )
    (net (code "102") (name "unconnected-(U1-NC-Pad21)") (class "Default")
      (node (ref "U1") (pin "21") (pinfunction "NC_21") (pintype "no_connect"))
    )
    (net (code "103") (name "unconnected-(U1-NC-Pad28)") (class "Default")
      (node (ref "U1") (pin "28") (pinfunction "NC_28") (pintype "no_connect"))
    )
    (net (code "104") (name "unconnected-(U1-NC-Pad32)") (class "Default")
      (node (ref "U1") (pin "32") (pinfunction "NC_32") (pintype "no_connect"))
    )
    (net (code "105") (name "unconnected-(U1-NC-Pad34)") (class "Default")
      (node (ref "U1") (pin "34") (pinfunction "NC_34") (pintype "no_connect"))
    )
    (net (code "106") (name "unconnected-(U1-NC-Pad36)") (class "Default")
      (node (ref "U1") (pin "36") (pinfunction "NC_36") (pintype "no_connect"))
    )
    (net (code "107") (name "unconnected-(U1-NC-Pad39)") (class "Default")
      (node (ref "U1") (pin "39") (pinfunction "NC_39") (pintype "no_connect"))
    )
    (net (code "108") (name "unconnected-(U1-SPI_CFG1-Pad37)") (class "Default")
      (node (ref "U1") (pin "37") (pinfunction "SPI_CFG1_37") (pintype "bidirectional"))
    )
    (net (code "109") (name "unconnected-(U1-TEST2-Pad27)") (class "Default")
      (node (ref "U1") (pin "27") (pinfunction "TEST2_27") (pintype "bidirectional"))
    )
    (net (code "110") (name "unconnected-(U1-TS_CAPT-Pad40)") (class "Default")
      (node (ref "U1") (pin "40") (pinfunction "TS_CAPT_40") (pintype "bidirectional"))
    )
    (net (code "111") (name "unconnected-(U1-TS_TIMER{slash}MS_SEL-Pad30)") (class "Default")
      (node (ref "U1") (pin "30") (pinfunction "TS_TIMER/MS_SEL_30") (pintype "bidirectional"))
    )
    (net (code "112") (name "unconnected-(U1-~{SWPD_EN}-Pad33)") (class "Default")
      (node (ref "U1") (pin "33") (pinfunction "~{SWPD_EN}_33") (pintype "bidirectional"))
    )
    (net (code "113") (name "unconnected-(U1-~{TX2P4_EN}-Pad31)") (class "Default")
      (node (ref "U1") (pin "31") (pinfunction "~{TX2P4_EN}_31") (pintype "bidirectional"))
    )
  )
)
